# B172C.net
KiCad netlist of a schematic drawn in EAGLE
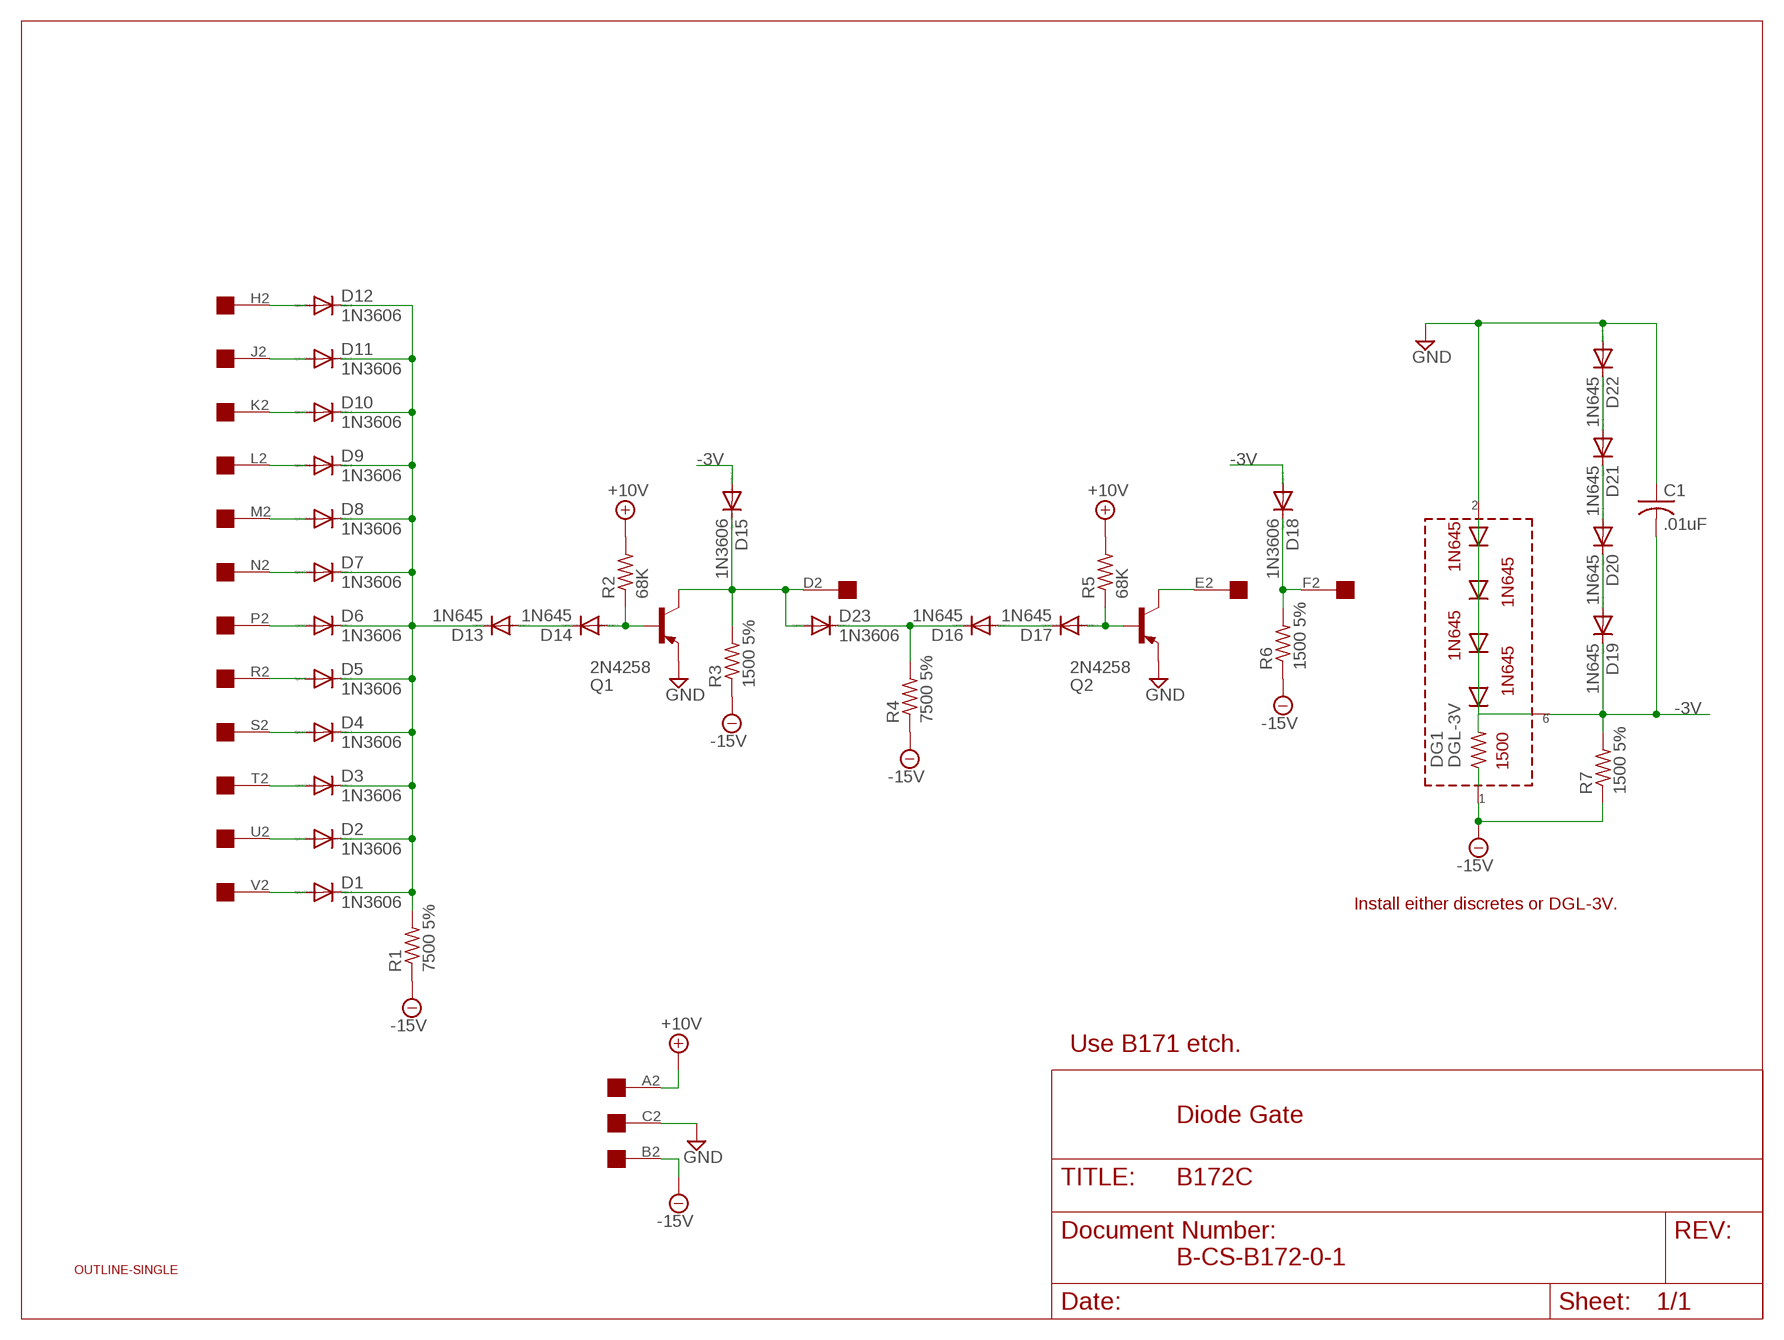
[diagram p0: schematic, sheet 1]

(export (version "E")
  (design (tool "Eeschema 10.0.6"))
  (components
    (comp (ref "C1")
      (value ".01uF")
      (footprint "eagle-import:C050-025X075")
      (libsource (lib "eagle-import") (part "C-US050-025X075"))
    )
    (comp (ref "D1")
      (value "1N3606")
      (footprint "eagle-import:DO35-10")
      (libsource (lib "eagle-import") (part "DIODE-DO35-10"))
    )
    (comp (ref "D2")
      (value "1N3606")
      (footprint "eagle-import:DO35-10")
      (libsource (lib "eagle-import") (part "DIODE-DO35-10"))
    )
    (comp (ref "D3")
      (value "1N3606")
      (footprint "eagle-import:DO35-10")
      (libsource (lib "eagle-import") (part "DIODE-DO35-10"))
    )
    (comp (ref "D4")
      (value "1N3606")
      (footprint "eagle-import:DO35-10")
      (libsource (lib "eagle-import") (part "DIODE-DO35-10"))
    )
    (comp (ref "D5")
      (value "1N3606")
      (footprint "eagle-import:DO35-10")
      (libsource (lib "eagle-import") (part "DIODE-DO35-10"))
    )
    (comp (ref "D6")
      (value "1N3606")
      (footprint "eagle-import:DO35-10")
      (libsource (lib "eagle-import") (part "DIODE-DO35-10"))
    )
    (comp (ref "D7")
      (value "1N3606")
      (footprint "eagle-import:DO35-10")
      (libsource (lib "eagle-import") (part "DIODE-DO35-10"))
    )
    (comp (ref "D8")
      (value "1N3606")
      (footprint "eagle-import:DO35-10")
      (libsource (lib "eagle-import") (part "DIODE-DO35-10"))
    )
    (comp (ref "D9")
      (value "1N3606")
      (footprint "eagle-import:DO35-10")
      (libsource (lib "eagle-import") (part "DIODE-DO35-10"))
    )
    (comp (ref "D10")
      (value "1N3606")
      (footprint "eagle-import:DO35-10")
      (libsource (lib "eagle-import") (part "DIODE-DO35-10"))
    )
    (comp (ref "D11")
      (value "1N3606")
      (footprint "eagle-import:DO35-10")
      (libsource (lib "eagle-import") (part "DIODE-DO35-10"))
    )
    (comp (ref "D12")
      (value "1N3606")
      (footprint "eagle-import:DO35-10")
      (libsource (lib "eagle-import") (part "DIODE-DO35-10"))
    )
    (comp (ref "D13")
      (value "1N645")
      (footprint "eagle-import:DO35-10")
      (libsource (lib "eagle-import") (part "DIODE-DO35-10"))
    )
    (comp (ref "D14")
      (value "1N645")
      (footprint "eagle-import:DO35-10")
      (libsource (lib "eagle-import") (part "DIODE-DO35-10"))
    )
    (comp (ref "D15")
      (value "1N3606")
      (footprint "eagle-import:DO35-10")
      (libsource (lib "eagle-import") (part "DIODE-DO35-10"))
    )
    (comp (ref "D16")
      (value "1N645")
      (footprint "eagle-import:DO35-10")
      (libsource (lib "eagle-import") (part "DIODE-DO35-10"))
    )
    (comp (ref "D17")
      (value "1N645")
      (footprint "eagle-import:DO35-10")
      (libsource (lib "eagle-import") (part "DIODE-DO35-10"))
    )
    (comp (ref "D18")
      (value "1N3606")
      (footprint "eagle-import:DO35-10")
      (libsource (lib "eagle-import") (part "DIODE-DO35-10"))
    )
    (comp (ref "D19")
      (value "1N645")
      (footprint "eagle-import:DO35-10")
      (libsource (lib "eagle-import") (part "DIODE-DO35-10"))
    )
    (comp (ref "D20")
      (value "1N645")
      (footprint "eagle-import:DO35-10")
      (libsource (lib "eagle-import") (part "DIODE-DO35-10"))
    )
    (comp (ref "D21")
      (value "1N645")
      (footprint "eagle-import:DO35-10")
      (libsource (lib "eagle-import") (part "DIODE-DO35-10"))
    )
    (comp (ref "D22")
      (value "1N645")
      (footprint "eagle-import:DO35-10")
      (libsource (lib "eagle-import") (part "DIODE-DO35-10"))
    )
    (comp (ref "D23")
      (value "1N3606")
      (footprint "eagle-import:DO35-10")
      (libsource (lib "eagle-import") (part "DIODE-DO35-10"))
    )
    (comp (ref "DG1")
      (value "DGL-3V")
      (footprint "eagle-import:DGL2")
      (libsource (lib "eagle-import") (part "DGL-3V"))
    )
    (comp (ref "Q1")
      (value "2N4258")
      (footprint "eagle-import:TO5")
      (libsource (lib "eagle-import") (part "-PNP-TO5"))
    )
    (comp (ref "Q2")
      (value "2N4258")
      (footprint "eagle-import:TO5")
      (libsource (lib "eagle-import") (part "-PNP-TO5"))
    )
    (comp (ref "R1")
      (value "7500 5%")
      (footprint "eagle-import:0207_10")
      (libsource (lib "eagle-import") (part "R-US_0207/10"))
    )
    (comp (ref "R2")
      (value "68K")
      (footprint "eagle-import:0207_10")
      (libsource (lib "eagle-import") (part "R-US_0207/10"))
    )
    (comp (ref "R3")
      (value "1500 5%")
      (footprint "eagle-import:0207_10")
      (libsource (lib "eagle-import") (part "R-US_0207/10"))
    )
    (comp (ref "R4")
      (value "7500 5%")
      (footprint "eagle-import:0207_10")
      (libsource (lib "eagle-import") (part "R-US_0207/10"))
    )
    (comp (ref "R5")
      (value "68K")
      (footprint "eagle-import:0207_10")
      (libsource (lib "eagle-import") (part "R-US_0207/10"))
    )
    (comp (ref "R6")
      (value "1500 5%")
      (footprint "eagle-import:0207_10")
      (libsource (lib "eagle-import") (part "R-US_0207/10"))
    )
    (comp (ref "R7")
      (value "1500 5%")
      (footprint "eagle-import:0207_10")
      (libsource (lib "eagle-import") (part "R-US_0207/10"))
    )
    (comp (ref "U$1")
      (value "OUTLINE-SINGLE")
      (footprint "eagle-import:SINGLE")
      (libsource (lib "eagle-import") (part "OUTLINE-SINGLE"))
    )
    (comp (ref "U$2")
      (value "EDGE-1")
      (footprint "eagle-import:EDGE-CON1")
      (libsource (lib "eagle-import") (part "EDGE-1"))
    )
  )
  (nets
    (net (code "1") (name "+10V") (class "Default")
      (node (ref "R2") (pin "2") (pinfunction "2_2") (pintype "passive"))
      (node (ref "R5") (pin "2") (pinfunction "2_2") (pintype "passive"))
      (node (ref "U$2") (pin "A2") (pinfunction "1_A2") (pintype "bidirectional"))
    )
    (net (code "2") (name "-15V") (class "Default")
      (node (ref "DG1") (pin "P$1") (pinfunction "1_P$1") (pintype "passive"))
      (node (ref "R1") (pin "1") (pinfunction "1_1") (pintype "passive"))
      (node (ref "R3") (pin "1") (pinfunction "1_1") (pintype "passive"))
      (node (ref "R4") (pin "1") (pinfunction "1_1") (pintype "passive"))
      (node (ref "R6") (pin "1") (pinfunction "1_1") (pintype "passive"))
      (node (ref "R7") (pin "1") (pinfunction "1_1") (pintype "passive"))
      (node (ref "U$2") (pin "B2") (pinfunction "1_B2") (pintype "bidirectional"))
    )
    (net (code "3") (name "/-3V") (class "Default")
      (node (ref "C1") (pin "2") (pinfunction "2_2") (pintype "passive"))
      (node (ref "D15") (pin "A") (pinfunction "A_A") (pintype "passive"))
      (node (ref "D18") (pin "A") (pinfunction "A_A") (pintype "passive"))
      (node (ref "D19") (pin "C") (pinfunction "C_C") (pintype "passive"))
      (node (ref "DG1") (pin "P$6") (pinfunction "6_P$6") (pintype "passive"))
      (node (ref "R7") (pin "2") (pinfunction "2_2") (pintype "passive"))
    )
    (net (code "4") (name "GND") (class "Default")
      (node (ref "C1") (pin "1") (pinfunction "1_1") (pintype "passive"))
      (node (ref "D22") (pin "A") (pinfunction "A_A") (pintype "passive"))
      (node (ref "DG1") (pin "P$2") (pinfunction "2_P$2") (pintype "passive"))
      (node (ref "Q1") (pin "1") (pinfunction "E_1") (pintype "passive"))
      (node (ref "Q2") (pin "1") (pinfunction "E_1") (pintype "passive"))
      (node (ref "U$2") (pin "C2") (pinfunction "1_C2") (pintype "bidirectional"))
    )
    (net (code "5") (name "Net-(D1-PadC)") (class "Default")
      (node (ref "D1") (pin "C") (pinfunction "C_C") (pintype "passive"))
      (node (ref "D10") (pin "C") (pinfunction "C_C") (pintype "passive"))
      (node (ref "D11") (pin "C") (pinfunction "C_C") (pintype "passive"))
      (node (ref "D12") (pin "C") (pinfunction "C_C") (pintype "passive"))
      (node (ref "D13") (pin "C") (pinfunction "C_C") (pintype "passive"))
      (node (ref "D2") (pin "C") (pinfunction "C_C") (pintype "passive"))
      (node (ref "D3") (pin "C") (pinfunction "C_C") (pintype "passive"))
      (node (ref "D4") (pin "C") (pinfunction "C_C") (pintype "passive"))
      (node (ref "D5") (pin "C") (pinfunction "C_C") (pintype "passive"))
      (node (ref "D6") (pin "C") (pinfunction "C_C") (pintype "passive"))
      (node (ref "D7") (pin "C") (pinfunction "C_C") (pintype "passive"))
      (node (ref "D8") (pin "C") (pinfunction "C_C") (pintype "passive"))
      (node (ref "D9") (pin "C") (pinfunction "C_C") (pintype "passive"))
      (node (ref "R1") (pin "2") (pinfunction "2_2") (pintype "passive"))
    )
    (net (code "6") (name "Net-(D13-PadA)") (class "Default")
      (node (ref "D13") (pin "A") (pinfunction "A_A") (pintype "passive"))
      (node (ref "D14") (pin "C") (pinfunction "C_C") (pintype "passive"))
    )
    (net (code "7") (name "Net-(D16-PadA)") (class "Default")
      (node (ref "D16") (pin "A") (pinfunction "A_A") (pintype "passive"))
      (node (ref "D17") (pin "C") (pinfunction "C_C") (pintype "passive"))
    )
    (net (code "8") (name "Net-(D16-PadC)") (class "Default")
      (node (ref "D16") (pin "C") (pinfunction "C_C") (pintype "passive"))
      (node (ref "D23") (pin "C") (pinfunction "C_C") (pintype "passive"))
      (node (ref "R4") (pin "2") (pinfunction "2_2") (pintype "passive"))
    )
    (net (code "9") (name "Net-(D19-PadA)") (class "Default")
      (node (ref "D19") (pin "A") (pinfunction "A_A") (pintype "passive"))
      (node (ref "D20") (pin "C") (pinfunction "C_C") (pintype "passive"))
    )
    (net (code "10") (name "Net-(D20-PadA)") (class "Default")
      (node (ref "D20") (pin "A") (pinfunction "A_A") (pintype "passive"))
      (node (ref "D21") (pin "C") (pinfunction "C_C") (pintype "passive"))
    )
    (net (code "11") (name "Net-(D21-PadA)") (class "Default")
      (node (ref "D21") (pin "A") (pinfunction "A_A") (pintype "passive"))
      (node (ref "D22") (pin "C") (pinfunction "C_C") (pintype "passive"))
    )
    (net (code "12") (name "Net-(Q1-B)") (class "Default")
      (node (ref "D14") (pin "A") (pinfunction "A_A") (pintype "passive"))
      (node (ref "Q1") (pin "2") (pinfunction "B_2") (pintype "passive"))
      (node (ref "R2") (pin "1") (pinfunction "1_1") (pintype "passive"))
    )
    (net (code "13") (name "Net-(Q1-C)") (class "Default")
      (node (ref "D15") (pin "C") (pinfunction "C_C") (pintype "passive"))
      (node (ref "D23") (pin "A") (pinfunction "A_A") (pintype "passive"))
      (node (ref "Q1") (pin "3") (pinfunction "C_3") (pintype "passive"))
      (node (ref "R3") (pin "2") (pinfunction "2_2") (pintype "passive"))
      (node (ref "U$2") (pin "D2") (pinfunction "1_D2") (pintype "bidirectional"))
    )
    (net (code "14") (name "Net-(Q2-B)") (class "Default")
      (node (ref "D17") (pin "A") (pinfunction "A_A") (pintype "passive"))
      (node (ref "Q2") (pin "2") (pinfunction "B_2") (pintype "passive"))
      (node (ref "R5") (pin "1") (pinfunction "1_1") (pintype "passive"))
    )
    (net (code "15") (name "Net-(Q2-C)") (class "Default")
      (node (ref "Q2") (pin "3") (pinfunction "C_3") (pintype "passive"))
      (node (ref "U$2") (pin "E2") (pinfunction "1_E2") (pintype "bidirectional"))
    )
    (net (code "16") (name "Net-(U$2F-1)") (class "Default")
      (node (ref "D18") (pin "C") (pinfunction "C_C") (pintype "passive"))
      (node (ref "R6") (pin "2") (pinfunction "2_2") (pintype "passive"))
      (node (ref "U$2") (pin "F2") (pinfunction "1_F2") (pintype "bidirectional"))
    )
    (net (code "17") (name "Net-(U$2G-1)") (class "Default")
      (node (ref "D12") (pin "A") (pinfunction "A_A") (pintype "passive"))
      (node (ref "U$2") (pin "H2") (pinfunction "1_H2") (pintype "bidirectional"))
    )
    (net (code "18") (name "Net-(U$2H-1)") (class "Default")
      (node (ref "D11") (pin "A") (pinfunction "A_A") (pintype "passive"))
      (node (ref "U$2") (pin "J2") (pinfunction "1_J2") (pintype "bidirectional"))
    )
    (net (code "19") (name "Net-(U$2I-1)") (class "Default")
      (node (ref "D10") (pin "A") (pinfunction "A_A") (pintype "passive"))
      (node (ref "U$2") (pin "K2") (pinfunction "1_K2") (pintype "bidirectional"))
    )
    (net (code "20") (name "Net-(U$2J-1)") (class "Default")
      (node (ref "D9") (pin "A") (pinfunction "A_A") (pintype "passive"))
      (node (ref "U$2") (pin "L2") (pinfunction "1_L2") (pintype "bidirectional"))
    )
    (net (code "21") (name "Net-(U$2K-1)") (class "Default")
      (node (ref "D8") (pin "A") (pinfunction "A_A") (pintype "passive"))
      (node (ref "U$2") (pin "M2") (pinfunction "1_M2") (pintype "bidirectional"))
    )
    (net (code "22") (name "Net-(U$2L-1)") (class "Default")
      (node (ref "D7") (pin "A") (pinfunction "A_A") (pintype "passive"))
      (node (ref "U$2") (pin "N2") (pinfunction "1_N2") (pintype "bidirectional"))
    )
    (net (code "23") (name "Net-(U$2M-1)") (class "Default")
      (node (ref "D6") (pin "A") (pinfunction "A_A") (pintype "passive"))
      (node (ref "U$2") (pin "P2") (pinfunction "1_P2") (pintype "bidirectional"))
    )
    (net (code "24") (name "Net-(U$2N-1)") (class "Default")
      (node (ref "D5") (pin "A") (pinfunction "A_A") (pintype "passive"))
      (node (ref "U$2") (pin "R2") (pinfunction "1_R2") (pintype "bidirectional"))
    )
    (net (code "25") (name "Net-(U$2O-1)") (class "Default")
      (node (ref "D4") (pin "A") (pinfunction "A_A") (pintype "passive"))
      (node (ref "U$2") (pin "S2") (pinfunction "1_S2") (pintype "bidirectional"))
    )
    (net (code "26") (name "Net-(U$2P-1)") (class "Default")
      (node (ref "D3") (pin "A") (pinfunction "A_A") (pintype "passive"))
      (node (ref "U$2") (pin "T2") (pinfunction "1_T2") (pintype "bidirectional"))
    )
    (net (code "27") (name "Net-(U$2Q-1)") (class "Default")
      (node (ref "D2") (pin "A") (pinfunction "A_A") (pintype "passive"))
      (node (ref "U$2") (pin "U2") (pinfunction "1_U2") (pintype "bidirectional"))
    )
    (net (code "28") (name "Net-(U$2R-1)") (class "Default")
      (node (ref "D1") (pin "A") (pinfunction "A_A") (pintype "passive"))
      (node (ref "U$2") (pin "V2") (pinfunction "1_V2") (pintype "bidirectional"))
    )
  )
)
